# CompensationRegression.net
KiCad netlist of a schematic drawn in Altium Designer
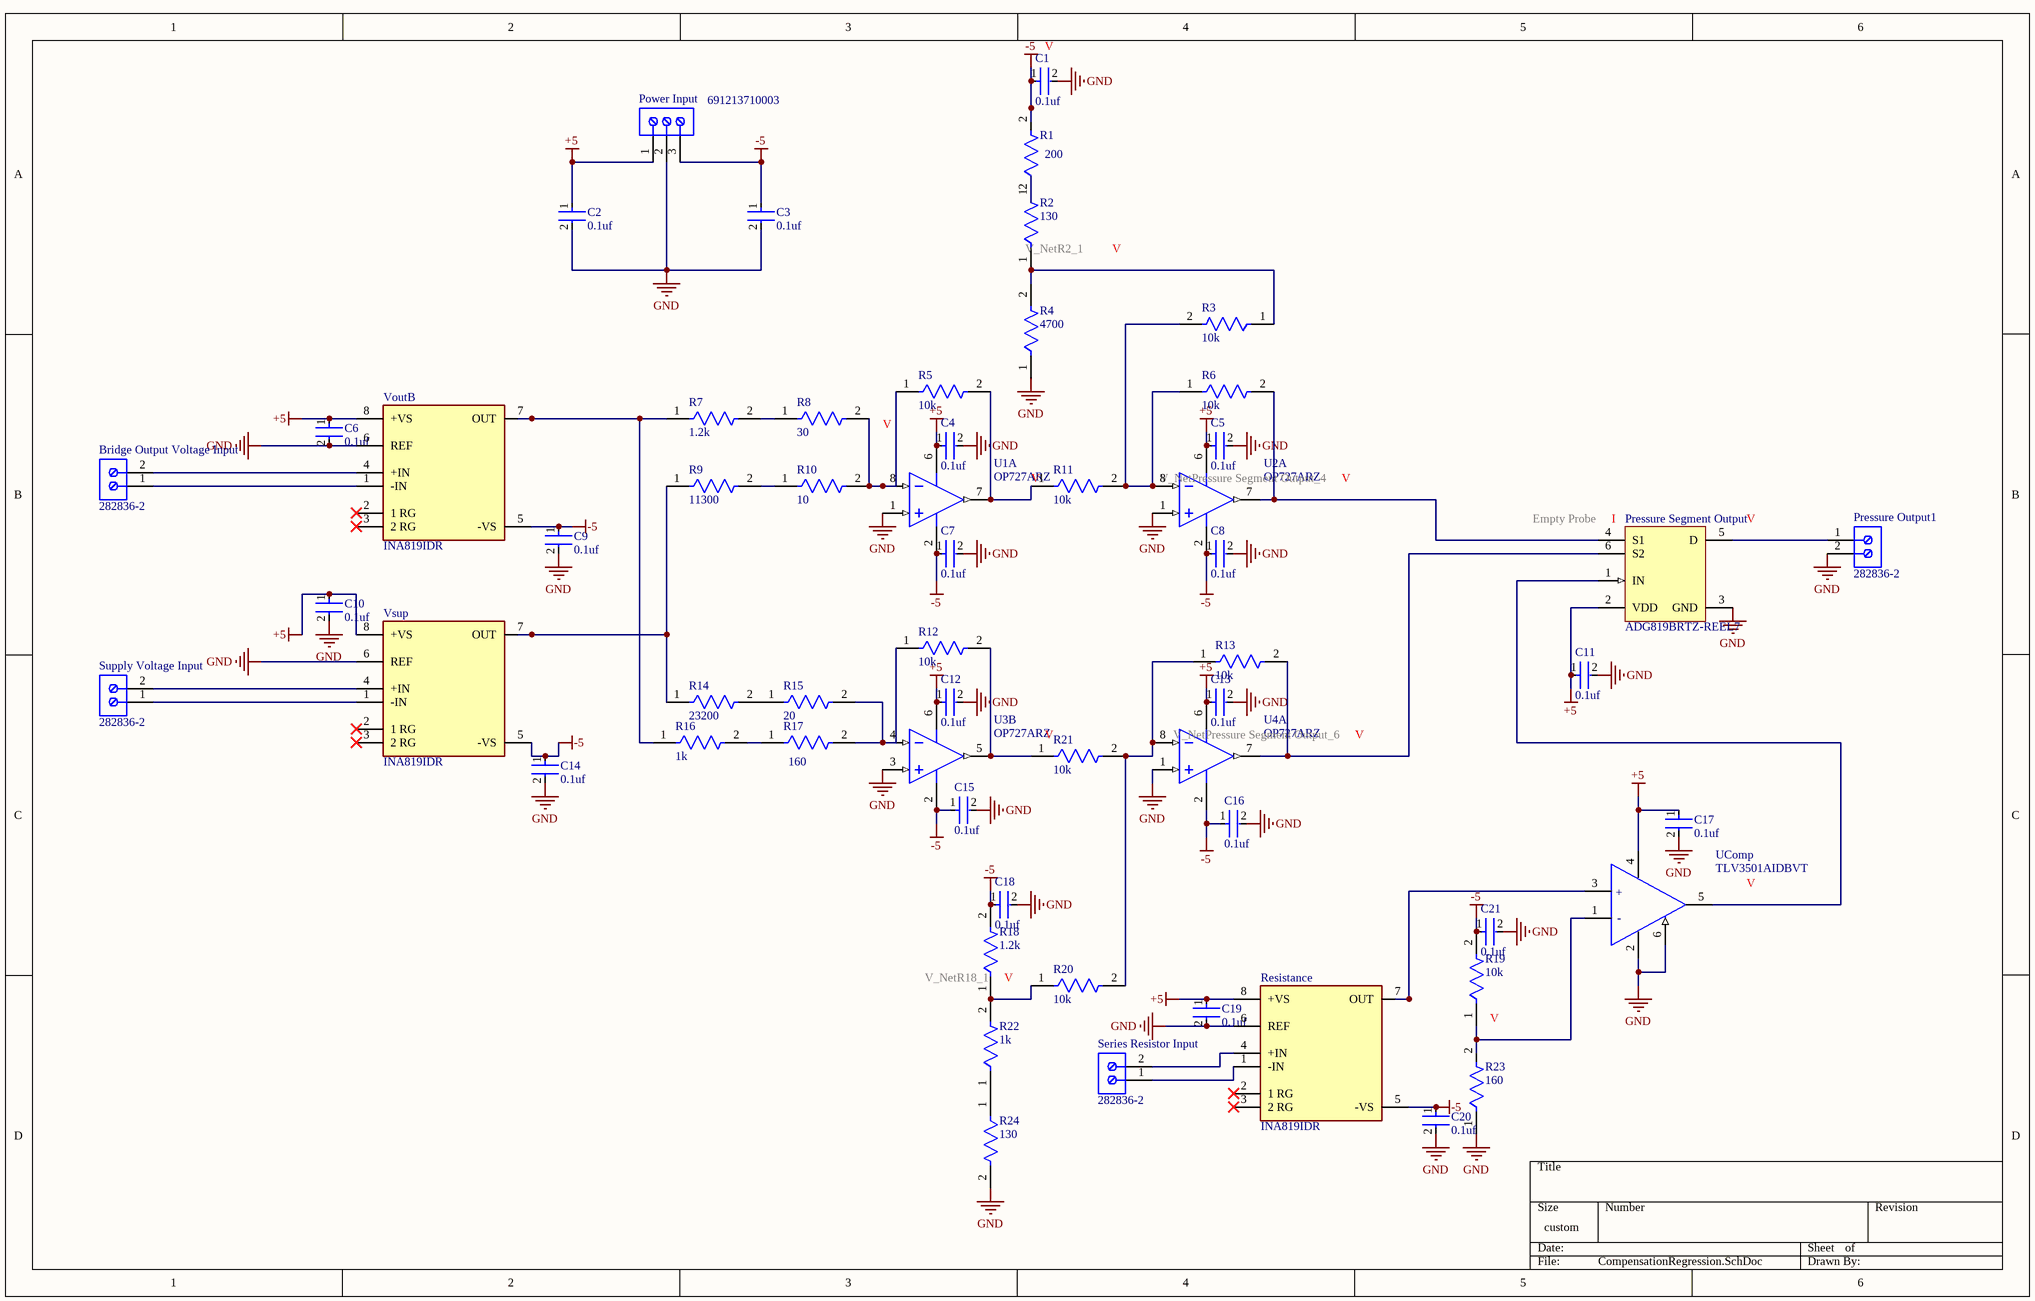
[diagram p0: CompensationRegression.SchDoc]

(export (version "E")
  (design (tool "Eeschema 10.0.6"))
  (components
    (comp (ref "Bridge Output Voltage Input")
      (value "282836-2")
      (footprint "TECO-282836-2_V")
      (description "Female Header, Pitch 5 mm, 1 x 2 Position, Height 10 mm, Tail Length 3.5 mm, Rohs, Bulk")
      (fields (field (name "VOLTAGE") "300V") (field (name "MANUFACTURER") "TE Connectivity"))
      (libsource (lib "Altium Content Vault") (part "CN-1P-F-TB2"))
    )
    (comp (ref "C1")
      (value "0.1uf")
      (footprint "FP-C0603C-CF-MFG")
      (description "CAP CER 0.1UF 50V X7R 0603")
      (fields (field (name "TOLERANCE") "0.1") (field (name "MANUFACTURER") "KEMET"))
      (libsource (lib "Altium Content Vault") (part "b4654b650e69147ec39a6b967a45e02"))
    )
    (comp (ref "C2")
      (value "0.1uf")
      (footprint "FP-C0603C-CF-MFG")
      (description "CAP CER 0.1UF 50V X7R 0603")
      (fields (field (name "TOLERANCE") "0.1") (field (name "MANUFACTURER") "KEMET"))
      (libsource (lib "Altium Content Vault") (part "b4654b650e69147ec39a6b967a45e02"))
    )
    (comp (ref "C3")
      (value "0.1uf")
      (footprint "FP-C0603C-CF-MFG")
      (description "CAP CER 0.1UF 50V X7R 0603")
      (fields (field (name "TOLERANCE") "0.1") (field (name "MANUFACTURER") "KEMET"))
      (libsource (lib "Altium Content Vault") (part "b4654b650e69147ec39a6b967a45e02"))
    )
    (comp (ref "C4")
      (value "0.1uf")
      (footprint "FP-C0603C-CF-MFG")
      (description "CAP CER 0.1UF 50V X7R 0603")
      (fields (field (name "TOLERANCE") "0.1") (field (name "MANUFACTURER") "KEMET"))
      (libsource (lib "Altium Content Vault") (part "b4654b650e69147ec39a6b967a45e02"))
    )
    (comp (ref "C5")
      (value "0.1uf")
      (footprint "FP-C0603C-CF-MFG")
      (description "CAP CER 0.1UF 50V X7R 0603")
      (fields (field (name "TOLERANCE") "0.1") (field (name "MANUFACTURER") "KEMET"))
      (libsource (lib "Altium Content Vault") (part "b4654b650e69147ec39a6b967a45e02"))
    )
    (comp (ref "C6")
      (value "0.1uf")
      (footprint "FP-C0603C-CF-MFG")
      (description "CAP CER 0.1UF 50V X7R 0603")
      (fields (field (name "TOLERANCE") "0.1") (field (name "MANUFACTURER") "KEMET"))
      (libsource (lib "Altium Content Vault") (part "b4654b650e69147ec39a6b967a45e02"))
    )
    (comp (ref "C7")
      (value "0.1uf")
      (footprint "FP-C0603C-CF-MFG")
      (description "CAP CER 0.1UF 50V X7R 0603")
      (fields (field (name "TOLERANCE") "0.1") (field (name "MANUFACTURER") "KEMET"))
      (libsource (lib "Altium Content Vault") (part "b4654b650e69147ec39a6b967a45e02"))
    )
    (comp (ref "C8")
      (value "0.1uf")
      (footprint "FP-C0603C-CF-MFG")
      (description "CAP CER 0.1UF 50V X7R 0603")
      (fields (field (name "TOLERANCE") "0.1") (field (name "MANUFACTURER") "KEMET"))
      (libsource (lib "Altium Content Vault") (part "b4654b650e69147ec39a6b967a45e02"))
    )
    (comp (ref "C9")
      (value "0.1uf")
      (footprint "FP-C0603C-CF-MFG")
      (description "CAP CER 0.1UF 50V X7R 0603")
      (fields (field (name "TOLERANCE") "0.1") (field (name "MANUFACTURER") "KEMET"))
      (libsource (lib "Altium Content Vault") (part "b4654b650e69147ec39a6b967a45e02"))
    )
    (comp (ref "C10")
      (value "0.1uf")
      (footprint "FP-C0603C-CF-MFG")
      (description "CAP CER 0.1UF 50V X7R 0603")
      (fields (field (name "TOLERANCE") "0.1") (field (name "MANUFACTURER") "KEMET"))
      (libsource (lib "Altium Content Vault") (part "b4654b650e69147ec39a6b967a45e02"))
    )
    (comp (ref "C11")
      (value "0.1uf")
      (footprint "FP-C0603C-CF-MFG")
      (description "CAP CER 0.1UF 50V X7R 0603")
      (fields (field (name "TOLERANCE") "0.1") (field (name "MANUFACTURER") "KEMET"))
      (libsource (lib "Altium Content Vault") (part "b4654b650e69147ec39a6b967a45e02"))
    )
    (comp (ref "C12")
      (value "0.1uf")
      (footprint "FP-C0603C-CF-MFG")
      (description "CAP CER 0.1UF 50V X7R 0603")
      (fields (field (name "TOLERANCE") "0.1") (field (name "MANUFACTURER") "KEMET"))
      (libsource (lib "Altium Content Vault") (part "b4654b650e69147ec39a6b967a45e02"))
    )
    (comp (ref "C13")
      (value "0.1uf")
      (footprint "FP-C0603C-CF-MFG")
      (description "CAP CER 0.1UF 50V X7R 0603")
      (fields (field (name "TOLERANCE") "0.1") (field (name "MANUFACTURER") "KEMET"))
      (libsource (lib "Altium Content Vault") (part "b4654b650e69147ec39a6b967a45e02"))
    )
    (comp (ref "C14")
      (value "0.1uf")
      (footprint "FP-C0603C-CF-MFG")
      (description "CAP CER 0.1UF 50V X7R 0603")
      (fields (field (name "TOLERANCE") "0.1") (field (name "MANUFACTURER") "KEMET"))
      (libsource (lib "Altium Content Vault") (part "b4654b650e69147ec39a6b967a45e02"))
    )
    (comp (ref "C15")
      (value "0.1uf")
      (footprint "FP-C0603C-CF-MFG")
      (description "CAP CER 0.1UF 50V X7R 0603")
      (fields (field (name "TOLERANCE") "0.1") (field (name "MANUFACTURER") "KEMET"))
      (libsource (lib "Altium Content Vault") (part "b4654b650e69147ec39a6b967a45e02"))
    )
    (comp (ref "C16")
      (value "0.1uf")
      (footprint "FP-C0603C-CF-MFG")
      (description "CAP CER 0.1UF 50V X7R 0603")
      (fields (field (name "TOLERANCE") "0.1") (field (name "MANUFACTURER") "KEMET"))
      (libsource (lib "Altium Content Vault") (part "b4654b650e69147ec39a6b967a45e02"))
    )
    (comp (ref "C17")
      (value "0.1uf")
      (footprint "FP-C0603C-CF-MFG")
      (description "CAP CER 0.1UF 50V X7R 0603")
      (fields (field (name "TOLERANCE") "0.1") (field (name "MANUFACTURER") "KEMET"))
      (libsource (lib "Altium Content Vault") (part "b4654b650e69147ec39a6b967a45e02"))
    )
    (comp (ref "C18")
      (value "0.1uf")
      (footprint "FP-C0603C-CF-MFG")
      (description "CAP CER 0.1UF 50V X7R 0603")
      (fields (field (name "TOLERANCE") "0.1") (field (name "MANUFACTURER") "KEMET"))
      (libsource (lib "Altium Content Vault") (part "b4654b650e69147ec39a6b967a45e02"))
    )
    (comp (ref "C19")
      (value "0.1uf")
      (footprint "FP-C0603C-CF-MFG")
      (description "CAP CER 0.1UF 50V X7R 0603")
      (fields (field (name "TOLERANCE") "0.1") (field (name "MANUFACTURER") "KEMET"))
      (libsource (lib "Altium Content Vault") (part "b4654b650e69147ec39a6b967a45e02"))
    )
    (comp (ref "C20")
      (value "0.1uf")
      (footprint "FP-C0603C-CF-MFG")
      (description "CAP CER 0.1UF 50V X7R 0603")
      (fields (field (name "TOLERANCE") "0.1") (field (name "MANUFACTURER") "KEMET"))
      (libsource (lib "Altium Content Vault") (part "b4654b650e69147ec39a6b967a45e02"))
    )
    (comp (ref "C21")
      (value "0.1uf")
      (footprint "FP-C0603C-CF-MFG")
      (description "CAP CER 0.1UF 50V X7R 0603")
      (fields (field (name "TOLERANCE") "0.1") (field (name "MANUFACTURER") "KEMET"))
      (libsource (lib "Altium Content Vault") (part "b4654b650e69147ec39a6b967a45e02"))
    )
    (comp (ref "Power Input")
      (value "691213710003")
      (footprint "691213710003")
      (fields (field (name "VOLTAGE") "300V"))
      (libsource (lib "Altium Content Vault") (part "TBL - 1R - 03P - Screw"))
    )
    (comp (ref "Pressure Output1")
      (value "282836-2")
      (footprint "TECO-282836-2_V")
      (description "Female Header, Pitch 5 mm, 1 x 2 Position, Height 10 mm, Tail Length 3.5 mm, Rohs, Bulk")
      (fields (field (name "VOLTAGE") "300V") (field (name "MANUFACTURER") "TE Connectivity"))
      (libsource (lib "Altium Content Vault") (part "CN-1P-F-TB2"))
    )
    (comp (ref "Pressure Segment Output")
      (value "ADG819BRTZ-REEL7")
      (footprint "ADI-RJ-6_N")
      (description "0.5 Ohm, CMOS, 1.8 to 5.5 V, 2:1 Mux / SPDT Switch, -40 to 125 degC, 6-pin SOT23 (RJ-6), Reel")
      (fields (field (name "MANUFACTURER") "Analog Devices"))
      (libsource (lib "Altium Content Vault") (part "ADI-ADG819-RJ-6"))
    )
    (comp (ref "R1")
      (value "200")
      (footprint "FP-CRCW0603-e3-MFG")
      (description "RES Thick Film, 200Ω, 1%, 0.1W, 100ppm/°C, 0603")
      (fields (field (name "TOLERANCE") "1%"))
      (libsource (lib "Altium Content Vault") (part "1029c3af85768c4190bb7ad29bc67b5"))
    )
    (comp (ref "R2")
      (value "130")
      (footprint "FP-CRCW0603-e3-MFG")
      (description "RES Thick Film, 130Ω, 1%, 0.1W, 100ppm/°C, 0603")
      (fields (field (name "TOLERANCE") "1%"))
      (libsource (lib "Altium Content Vault") (part "1029c3af85768c4190bb7ad29bc67b5"))
    )
    (comp (ref "R3")
      (value "10k")
      (footprint "FP-RT0603-MFG")
      (description "RES SMD 10K OHM 1% 1/10W 0603")
      (fields
        (field (name "MANUFACTURER") "Yageo")
        (field (name "OCTOPART") "https://octopart.com/rt0603fre0710kl-yageo-40009243")
      )
      (libsource (lib "Altium Content Vault") (part "1029c3af85768c4190bb7ad29bc67b5"))
    )
    (comp (ref "R4")
      (value "4700")
      (footprint "FP-MCT0603-MFG")
      (description "RES SMD 100 OHM 1% 1/8W 0603")
      (fields (field (name "TOLERANCE") "0.1%"))
      (libsource (lib "Altium Content Vault") (part "1029c3af85768c4190bb7ad29bc67b5"))
    )
    (comp (ref "R5")
      (value "10k")
      (footprint "FP-RT0603-MFG")
      (description "RES SMD 10K OHM 1% 1/10W 0603")
      (fields
        (field (name "MANUFACTURER") "Yageo")
        (field (name "OCTOPART") "https://octopart.com/rt0603fre0710kl-yageo-40009243")
      )
      (libsource (lib "Altium Content Vault") (part "1029c3af85768c4190bb7ad29bc67b5"))
    )
    (comp (ref "R6")
      (value "10k")
      (footprint "FP-RT0603-MFG")
      (description "RES SMD 10K OHM 1% 1/10W 0603")
      (fields
        (field (name "MANUFACTURER") "Yageo")
        (field (name "OCTOPART") "https://octopart.com/rt0603fre0710kl-yageo-40009243")
      )
      (libsource (lib "Altium Content Vault") (part "1029c3af85768c4190bb7ad29bc67b5"))
    )
    (comp (ref "R7")
      (value "1.2k")
      (footprint "FP-RG1005-IPC_A")
      (fields (field (name "TOLERANCE") "0.05%"))
      (libsource (lib "Altium Content Vault") (part "1029c3af85768c4190bb7ad29bc67b5"))
    )
    (comp (ref "R8")
      (value "30")
      (footprint "FP-CRCW0805-e3-MFG")
      (description "RES SMD 30 OHM 1% 1/8W 0805")
      (fields
        (field (name "OCTOPART") "https://octopart.com/crcw080530r0fkea-vishay-39861726")
        (field (name "TOLERANCE") "1%")
      )
      (libsource (lib "Altium Content Vault") (part "1029c3af85768c4190bb7ad29bc67b5"))
    )
    (comp (ref "R9")
      (value "11300")
      (footprint "FP-RP73P-1E-MFG")
      (description "RP73P 0402 11.3Ω 0.1W 25ppm/°C 0.10% 50V")
      (fields
        (field (name "MANUFACTURER") "TE Connectivity")
        (field (name "MANUFACTURER PART NUMBER") "RP73PF1E11R3BTDF")
      )
      (libsource (lib "Altium Content Vault") (part "1029c3af85768c4190bb7ad29bc67b5"))
    )
    (comp (ref "R10")
      (value "10")
      (footprint "FP-CRCW0603-e3-IPC_A")
      (description "RES Thick Film, 10Ω, 1%, 0.1W, 100ppm/°C, 0603")
      (fields (field (name "TOLERANCE") "1%"))
      (libsource (lib "Altium Content Vault") (part "1029c3af85768c4190bb7ad29bc67b5"))
    )
    (comp (ref "R11")
      (value "10k")
      (footprint "FP-RT0603-MFG")
      (description "RES SMD 10K OHM 1% 1/10W 0603")
      (fields
        (field (name "MANUFACTURER") "Yageo")
        (field (name "OCTOPART") "https://octopart.com/rt0603fre0710kl-yageo-40009243")
      )
      (libsource (lib "Altium Content Vault") (part "1029c3af85768c4190bb7ad29bc67b5"))
    )
    (comp (ref "R12")
      (value "10k")
      (footprint "FP-RT0603-MFG")
      (description "RES SMD 10K OHM 1% 1/10W 0603")
      (fields
        (field (name "MANUFACTURER") "Yageo")
        (field (name "OCTOPART") "https://octopart.com/rt0603fre0710kl-yageo-40009243")
      )
      (libsource (lib "Altium Content Vault") (part "1029c3af85768c4190bb7ad29bc67b5"))
    )
    (comp (ref "R13")
      (value "10k")
      (footprint "FP-RT0603-MFG")
      (description "RES SMD 10K OHM 1% 1/10W 0603")
      (fields
        (field (name "MANUFACTURER") "Yageo")
        (field (name "OCTOPART") "https://octopart.com/rt0603fre0710kl-yageo-40009243")
      )
      (libsource (lib "Altium Content Vault") (part "1029c3af85768c4190bb7ad29bc67b5"))
    )
    (comp (ref "R14")
      (value "23200")
      (footprint "FP-CRCW0603-e3-IPC_A")
      (description "RES Thick Film, 10Ω, 1%, 0.1W, 100ppm/°C, 0603\r\n\r\nShould be RMCF0603FT23K2")
      (fields (field (name "TOLERANCE") "1%"))
      (libsource (lib "Altium Content Vault") (part "1029c3af85768c4190bb7ad29bc67b5"))
    )
    (comp (ref "R15")
      (value "20")
      (footprint "FP-CRCW0402-e3-IPC_C")
      (description "RES Thick Film, 20Ω, 1%, 0.063W, 100ppm/°C, 0402")
      (fields (field (name "TOLERANCE") "1%"))
      (libsource (lib "Altium Content Vault") (part "1029c3af85768c4190bb7ad29bc67b5"))
    )
    (comp (ref "R16")
      (value "1k")
      (footprint "FP-CRCW0402-e3-MFG")
      (description "RES Thick Film, 1kΩ, 1%, 0.063W, 100ppm/°C, 0402")
      (fields (field (name "TOLERANCE") "1%"))
      (libsource (lib "Altium Content Vault") (part "1029c3af85768c4190bb7ad29bc67b5"))
    )
    (comp (ref "R17")
      (value "160")
      (footprint "FP-CRCW0402-e3-IPC_B")
      (description "RES Thick Film, 160Ω, 1%, 0.063W, 100ppm/°C, 0402")
      (fields (field (name "TOLERANCE") "1%"))
      (libsource (lib "Altium Content Vault") (part "1029c3af85768c4190bb7ad29bc67b5"))
    )
    (comp (ref "R18")
      (value "1.2k")
      (footprint "FP-RG1005-IPC_A")
      (description "Automotive Metal Thin Film Chip Resistor, 0402, 1.2kΩ, 0.05%, 25ppm/°C, 0.0625W, 75V")
      (fields (field (name "TOLERANCE") "0.05%"))
      (libsource (lib "Altium Content Vault") (part "1029c3af85768c4190bb7ad29bc67b5"))
    )
    (comp (ref "R19")
      (value "10k")
      (footprint "FP-RT0603-MFG")
      (description "RES SMD 10K OHM 1% 1/10W 0603")
      (fields
        (field (name "MANUFACTURER") "Yageo")
        (field (name "OCTOPART") "https://octopart.com/rt0603fre0710kl-yageo-40009243")
      )
      (libsource (lib "Altium Content Vault") (part "1029c3af85768c4190bb7ad29bc67b5"))
    )
    (comp (ref "R20")
      (value "10k")
      (footprint "FP-RT0603-MFG")
      (description "RES SMD 10K OHM 1% 1/10W 0603")
      (fields
        (field (name "MANUFACTURER") "Yageo")
        (field (name "OCTOPART") "https://octopart.com/rt0603fre0710kl-yageo-40009243")
      )
      (libsource (lib "Altium Content Vault") (part "1029c3af85768c4190bb7ad29bc67b5"))
    )
    (comp (ref "R21")
      (value "10k")
      (footprint "FP-RT0603-MFG")
      (description "RES SMD 10K OHM 1% 1/10W 0603")
      (fields
        (field (name "MANUFACTURER") "Yageo")
        (field (name "OCTOPART") "https://octopart.com/rt0603fre0710kl-yageo-40009243")
      )
      (libsource (lib "Altium Content Vault") (part "1029c3af85768c4190bb7ad29bc67b5"))
    )
    (comp (ref "R22")
      (value "1k")
      (footprint "FP-CRCW0402-e3-MFG")
      (description "RES Thick Film, 1kΩ, 1%, 0.063W, 100ppm/°C, 0402")
      (fields (field (name "TOLERANCE") "1%"))
      (libsource (lib "Altium Content Vault") (part "1029c3af85768c4190bb7ad29bc67b5"))
    )
    (comp (ref "R23")
      (value "160")
      (footprint "FP-CRCW0402-e3-IPC_B")
      (description "RES Thick Film, 160Ω, 1%, 0.063W, 100ppm/°C, 0402")
      (fields (field (name "TOLERANCE") "1%"))
      (libsource (lib "Altium Content Vault") (part "1029c3af85768c4190bb7ad29bc67b5"))
    )
    (comp (ref "R24")
      (value "130")
      (footprint "FP-CRCW0603-e3-MFG")
      (description "RES Thick Film, 130Ω, 1%, 0.1W, 100ppm/°C, 0603")
      (fields (field (name "TOLERANCE") "1%"))
      (libsource (lib "Altium Content Vault") (part "1029c3af85768c4190bb7ad29bc67b5"))
    )
    (comp (ref "Resistance")
      (value "INA819IDR")
      (footprint "FP-D0008A-MFG")
      (description "IC INST AMP 1 CIRCUIT 8SOIC")
      (libsource (lib "Altium Content Vault") (part "8571ca1dc6e78685731e0a9738c9e90"))
    )
    (comp (ref "Series Resistor Input")
      (value "282836-2")
      (footprint "TECO-282836-2_V")
      (description "Female Header, Pitch 5 mm, 1 x 2 Position, Height 10 mm, Tail Length 3.5 mm, Rohs, Bulk")
      (fields (field (name "VOLTAGE") "300V") (field (name "MANUFACTURER") "TE Connectivity"))
      (libsource (lib "Altium Content Vault") (part "CN-1P-F-TB2"))
    )
    (comp (ref "Supply Voltage Input")
      (value "282836-2")
      (footprint "TECO-282836-2_V")
      (description "Female Header, Pitch 5 mm, 1 x 2 Position, Height 10 mm, Tail Length 3.5 mm, Rohs, Bulk")
      (fields (field (name "VOLTAGE") "300V") (field (name "MANUFACTURER") "TE Connectivity"))
      (libsource (lib "Altium Content Vault") (part "CN-1P-F-TB2"))
    )
    (comp (ref "U1")
      (value "OP727ARZ")
      (footprint "ADI-R-8_L")
      (fields (field (name "GENERIC PART NUMBER") "OP727") (field (name "MANUFACTURER") "Analog Devices"))
      (libsource (lib "Altium Content Vault") (part "ADI-OP249_727-R-8"))
    )
    (comp (ref "U2")
      (value "OP727ARZ")
      (footprint "ADI-R-8_L")
      (fields (field (name "GENERIC PART NUMBER") "OP727") (field (name "MANUFACTURER") "Analog Devices"))
      (libsource (lib "Altium Content Vault") (part "ADI-OP249_727-R-8"))
    )
    (comp (ref "U3")
      (value "OP727ARZ")
      (footprint "ADI-R-8_L")
      (fields (field (name "GENERIC PART NUMBER") "OP727") (field (name "MANUFACTURER") "Analog Devices"))
      (libsource (lib "Altium Content Vault") (part "ADI-OP249_727-R-8"))
    )
    (comp (ref "U4")
      (value "OP727ARZ")
      (footprint "ADI-R-8_L")
      (fields (field (name "GENERIC PART NUMBER") "OP727") (field (name "MANUFACTURER") "Analog Devices"))
      (libsource (lib "Altium Content Vault") (part "ADI-OP249_727-R-8"))
    )
    (comp (ref "UComp")
      (value "TLV3501AIDBVT")
      (footprint "FP-DBV0006A-MFG")
      (description "IC COMP 4.5NS R-R HS SOT23-6")
      (fields
        (field (name "MANUFACTURER") "Texas Instruments")
        (field (name "OCTOPART") "https://octopart.com/tlv3501aidbvt-texas+instruments-428399")
      )
      (libsource (lib "Altium Content Vault") (part "0ecce7053b56ec2eec74f62614cfafa"))
    )
    (comp (ref "VoutB")
      (value "INA819IDR")
      (footprint "FP-D0008A-MFG")
      (description "IC INST AMP 1 CIRCUIT 8SOIC")
      (libsource (lib "Altium Content Vault") (part "8571ca1dc6e78685731e0a9738c9e90"))
    )
    (comp (ref "Vsup")
      (value "INA819IDR")
      (footprint "FP-D0008A-MFG")
      (description "IC INST AMP 1 CIRCUIT 8SOIC")
      (libsource (lib "Altium Content Vault") (part "8571ca1dc6e78685731e0a9738c9e90"))
    )
  )
  (nets
    (net (code "1") (name "+5") (class "Default")
      (node (ref "C10") (pin "1") (pinfunction "1_1") (pintype "passive"))
      (node (ref "C11") (pin "1") (pinfunction "1_1") (pintype "passive"))
      (node (ref "C12") (pin "1") (pinfunction "1_1") (pintype "passive"))
      (node (ref "C13") (pin "1") (pinfunction "1_1") (pintype "passive"))
      (node (ref "C17") (pin "1") (pinfunction "1_1") (pintype "passive"))
      (node (ref "C19") (pin "1") (pinfunction "1_1") (pintype "passive"))
      (node (ref "C2") (pin "1") (pinfunction "1_1") (pintype "passive"))
      (node (ref "C4") (pin "1") (pinfunction "1_1") (pintype "passive"))
      (node (ref "C5") (pin "1") (pinfunction "1_1") (pintype "passive"))
      (node (ref "C6") (pin "1") (pinfunction "1_1") (pintype "passive"))
      (node (ref "Power Input") (pin "1") (pinfunction "1_1") (pintype "passive"))
      (node (ref "Pressure Segment Output") (pin "2") (pinfunction "VDD_2") (pintype "power_in"))
      (node (ref "Resistance") (pin "8") (pinfunction "+VS_8") (pintype "power_in"))
      (node (ref "U1") (pin "6") (pinfunction "+V_6") (pintype "power_in"))
      (node (ref "U2") (pin "6") (pinfunction "+V_6") (pintype "power_in"))
      (node (ref "U3") (pin "6") (pinfunction "+V_6") (pintype "power_in"))
      (node (ref "U4") (pin "6") (pinfunction "+V_6") (pintype "power_in"))
      (node (ref "UComp") (pin "4") (pinfunction "V+_4") (pintype "power_in"))
      (node (ref "VoutB") (pin "8") (pinfunction "+VS_8") (pintype "power_in"))
      (node (ref "Vsup") (pin "8") (pinfunction "+VS_8") (pintype "power_in"))
    )
    (net (code "2") (name "-5") (class "Default")
      (node (ref "C1") (pin "1") (pinfunction "1_1") (pintype "passive"))
      (node (ref "C14") (pin "1") (pinfunction "1_1") (pintype "passive"))
      (node (ref "C15") (pin "1") (pinfunction "1_1") (pintype "passive"))
      (node (ref "C16") (pin "1") (pinfunction "1_1") (pintype "passive"))
      (node (ref "C18") (pin "1") (pinfunction "1_1") (pintype "passive"))
      (node (ref "C20") (pin "1") (pinfunction "1_1") (pintype "passive"))
      (node (ref "C21") (pin "1") (pinfunction "1_1") (pintype "passive"))
      (node (ref "C3") (pin "1") (pinfunction "1_1") (pintype "passive"))
      (node (ref "C7") (pin "1") (pinfunction "1_1") (pintype "passive"))
      (node (ref "C8") (pin "1") (pinfunction "1_1") (pintype "passive"))
      (node (ref "C9") (pin "1") (pinfunction "1_1") (pintype "passive"))
      (node (ref "Power Input") (pin "3") (pinfunction "3_3") (pintype "passive"))
      (node (ref "R1") (pin "2") (pinfunction "2_2") (pintype "passive"))
      (node (ref "R18") (pin "2") (pinfunction "2_2") (pintype "passive"))
      (node (ref "R19") (pin "2") (pinfunction "2_2") (pintype "passive"))
      (node (ref "Resistance") (pin "5") (pinfunction "-VS_5") (pintype "power_in"))
      (node (ref "U1") (pin "2") (pinfunction "-V_2") (pintype "power_in"))
      (node (ref "U2") (pin "2") (pinfunction "-V_2") (pintype "power_in"))
      (node (ref "U3") (pin "2") (pinfunction "-V_2") (pintype "power_in"))
      (node (ref "U4") (pin "2") (pinfunction "-V_2") (pintype "power_in"))
      (node (ref "VoutB") (pin "5") (pinfunction "-VS_5") (pintype "power_in"))
      (node (ref "Vsup") (pin "5") (pinfunction "-VS_5") (pintype "power_in"))
    )
    (net (code "3") (name "GND") (class "Default")
      (node (ref "C1") (pin "2") (pinfunction "2_2") (pintype "passive"))
      (node (ref "C10") (pin "2") (pinfunction "2_2") (pintype "passive"))
      (node (ref "C11") (pin "2") (pinfunction "2_2") (pintype "passive"))
      (node (ref "C12") (pin "2") (pinfunction "2_2") (pintype "passive"))
      (node (ref "C13") (pin "2") (pinfunction "2_2") (pintype "passive"))
      (node (ref "C14") (pin "2") (pinfunction "2_2") (pintype "passive"))
      (node (ref "C15") (pin "2") (pinfunction "2_2") (pintype "passive"))
      (node (ref "C16") (pin "2") (pinfunction "2_2") (pintype "passive"))
      (node (ref "C17") (pin "2") (pinfunction "2_2") (pintype "passive"))
      (node (ref "C18") (pin "2") (pinfunction "2_2") (pintype "passive"))
      (node (ref "C19") (pin "2") (pinfunction "2_2") (pintype "passive"))
      (node (ref "C2") (pin "2") (pinfunction "2_2") (pintype "passive"))
      (node (ref "C20") (pin "2") (pinfunction "2_2") (pintype "passive"))
      (node (ref "C21") (pin "2") (pinfunction "2_2") (pintype "passive"))
      (node (ref "C3") (pin "2") (pinfunction "2_2") (pintype "passive"))
      (node (ref "C4") (pin "2") (pinfunction "2_2") (pintype "passive"))
      (node (ref "C5") (pin "2") (pinfunction "2_2") (pintype "passive"))
      (node (ref "C6") (pin "2") (pinfunction "2_2") (pintype "passive"))
      (node (ref "C7") (pin "2") (pinfunction "2_2") (pintype "passive"))
      (node (ref "C8") (pin "2") (pinfunction "2_2") (pintype "passive"))
      (node (ref "C9") (pin "2") (pinfunction "2_2") (pintype "passive"))
      (node (ref "Power Input") (pin "2") (pinfunction "2_2") (pintype "passive"))
      (node (ref "Pressure Output1") (pin "2") (pinfunction "2_2") (pintype "passive"))
      (node (ref "Pressure Segment Output") (pin "3") (pinfunction "GND_3") (pintype "power_in"))
      (node (ref "R23") (pin "1") (pinfunction "1_1") (pintype "passive"))
      (node (ref "R24") (pin "2") (pinfunction "2_2") (pintype "passive"))
      (node (ref "R4") (pin "1") (pinfunction "1_1") (pintype "passive"))
      (node (ref "Resistance") (pin "6") (pinfunction "REF_6") (pintype "passive"))
      (node (ref "U1") (pin "1") (pinfunction "+IN_A_1") (pintype "input"))
      (node (ref "U2") (pin "1") (pinfunction "+IN_A_1") (pintype "input"))
      (node (ref "U3") (pin "3") (pinfunction "+IN_B_3") (pintype "input"))
      (node (ref "U4") (pin "1") (pinfunction "+IN_A_1") (pintype "input"))
      (node (ref "UComp") (pin "2") (pinfunction "V-_2") (pintype "power_in"))
      (node (ref "UComp") (pin "6") (pinfunction "SHDN_6") (pintype "input"))
      (node (ref "VoutB") (pin "6") (pinfunction "REF_6") (pintype "passive"))
      (node (ref "Vsup") (pin "6") (pinfunction "REF_6") (pintype "passive"))
    )
    (net (code "4") (name "Net-(Pressure Segment Output-D)") (class "Default")
      (node (ref "Pressure Output1") (pin "1") (pinfunction "1_1") (pintype "passive"))
      (node (ref "Pressure Segment Output") (pin "5") (pinfunction "D_5") (pintype "passive"))
    )
    (net (code "5") (name "Net-(Pressure Segment Output-IN)") (class "Default")
      (node (ref "Pressure Segment Output") (pin "1") (pinfunction "IN_1") (pintype "input"))
      (node (ref "UComp") (pin "5") (pinfunction "OUT_5") (pintype "passive"))
    )
    (net (code "6") (name "Net-(Pressure Segment Output-S1)") (class "Default")
      (node (ref "Pressure Segment Output") (pin "4") (pinfunction "S1_4") (pintype "passive"))
      (node (ref "R6") (pin "2") (pinfunction "2_2") (pintype "passive"))
      (node (ref "U2") (pin "7") (pinfunction "OUT_A_7") (pintype "output"))
    )
    (net (code "7") (name "Net-(Pressure Segment Output-S2)") (class "Default")
      (node (ref "Pressure Segment Output") (pin "6") (pinfunction "S2_6") (pintype "passive"))
      (node (ref "R13") (pin "2") (pinfunction "2_2") (pintype "passive"))
      (node (ref "U4") (pin "7") (pinfunction "OUT_A_7") (pintype "output"))
    )
    (net (code "8") (name "Net-(R1-Pad1)") (class "Default")
      (node (ref "R1") (pin "1") (pinfunction "1_1") (pintype "passive"))
      (node (ref "R2") (pin "2") (pinfunction "2_2") (pintype "passive"))
    )
    (net (code "9") (name "Net-(R2-Pad1)") (class "Default")
      (node (ref "R2") (pin "1") (pinfunction "1_1") (pintype "passive"))
      (node (ref "R3") (pin "1") (pinfunction "1_1") (pintype "passive"))
      (node (ref "R4") (pin "2") (pinfunction "2_2") (pintype "passive"))
    )
    (net (code "10") (name "Net-(R7-Pad2)") (class "Default")
      (node (ref "R7") (pin "2") (pinfunction "2_2") (pintype "passive"))
      (node (ref "R8") (pin "1") (pinfunction "1_1") (pintype "passive"))
    )
    (net (code "11") (name "Net-(R10-Pad1)") (class "Default")
      (node (ref "R10") (pin "1") (pinfunction "1_1") (pintype "passive"))
      (node (ref "R9") (pin "2") (pinfunction "2_2") (pintype "passive"))
    )
    (net (code "12") (name "Net-(R14-Pad2)") (class "Default")
      (node (ref "R14") (pin "2") (pinfunction "2_2") (pintype "passive"))
      (node (ref "R15") (pin "1") (pinfunction "1_1") (pintype "passive"))
    )
    (net (code "13") (name "Net-(R16-Pad2)") (class "Default")
      (node (ref "R16") (pin "2") (pinfunction "2_2") (pintype "passive"))
      (node (ref "R17") (pin "1") (pinfunction "1_1") (pintype "passive"))
    )
    (net (code "14") (name "Net-(R18-Pad1)") (class "Default")
      (node (ref "R18") (pin "1") (pinfunction "1_1") (pintype "passive"))
      (node (ref "R20") (pin "1") (pinfunction "1_1") (pintype "passive"))
      (node (ref "R22") (pin "2") (pinfunction "2_2") (pintype "passive"))
    )
    (net (code "15") (name "Net-(R22-Pad1)") (class "Default")
      (node (ref "R22") (pin "1") (pinfunction "1_1") (pintype "passive"))
      (node (ref "R24") (pin "1") (pinfunction "1_1") (pintype "passive"))
    )
    (net (code "16") (name "Net-(Resistance-+IN)") (class "Default")
      (node (ref "Resistance") (pin "4") (pinfunction "+IN_4") (pintype "tri_state"))
      (node (ref "Series Resistor Input") (pin "2") (pinfunction "2_2") (pintype "passive"))
    )
    (net (code "17") (name "Net-(Resistance--IN)") (class "Default")
      (node (ref "Resistance") (pin "1") (pinfunction "-IN_1") (pintype "tri_state"))
      (node (ref "Series Resistor Input") (pin "1") (pinfunction "1_1") (pintype "passive"))
    )
    (net (code "18") (name "Net-(Resistance-OUT)") (class "Default")
      (node (ref "Resistance") (pin "7") (pinfunction "OUT_7") (pintype "passive"))
      (node (ref "UComp") (pin "3") (pinfunction "+IN_3") (pintype "tri_state"))
    )
    (net (code "19") (name "Net-(U1A--IN_A)") (class "Default")
      (node (ref "R10") (pin "2") (pinfunction "2_2") (pintype "passive"))
      (node (ref "R5") (pin "1") (pinfunction "1_1") (pintype "passive"))
      (node (ref "R8") (pin "2") (pinfunction "2_2") (pintype "passive"))
      (node (ref "U1") (pin "8") (pinfunction "-IN_A_8") (pintype "input"))
    )
    (net (code "20") (name "Net-(U1A-OUT_A)") (class "Default")
      (node (ref "R11") (pin "1") (pinfunction "1_1") (pintype "passive"))
      (node (ref "R5") (pin "2") (pinfunction "2_2") (pintype "passive"))
      (node (ref "U1") (pin "7") (pinfunction "OUT_A_7") (pintype "output"))
    )
    (net (code "21") (name "Net-(U2A--IN_A)") (class "Default")
      (node (ref "R11") (pin "2") (pinfunction "2_2") (pintype "passive"))
      (node (ref "R3") (pin "2") (pinfunction "2_2") (pintype "passive"))
      (node (ref "R6") (pin "1") (pinfunction "1_1") (pintype "passive"))
      (node (ref "U2") (pin "8") (pinfunction "-IN_A_8") (pintype "input"))
    )
    (net (code "22") (name "Net-(U3B--IN_B)") (class "Default")
      (node (ref "R12") (pin "1") (pinfunction "1_1") (pintype "passive"))
      (node (ref "R15") (pin "2") (pinfunction "2_2") (pintype "passive"))
      (node (ref "R17") (pin "2") (pinfunction "2_2") (pintype "passive"))
      (node (ref "U3") (pin "4") (pinfunction "-IN_B_4") (pintype "input"))
    )
    (net (code "23") (name "Net-(U3B-OUT_B)") (class "Default")
      (node (ref "R12") (pin "2") (pinfunction "2_2") (pintype "passive"))
      (node (ref "R21") (pin "1") (pinfunction "1_1") (pintype "passive"))
      (node (ref "U3") (pin "5") (pinfunction "OUT_B_5") (pintype "output"))
    )
    (net (code "24") (name "Net-(U4A--IN_A)") (class "Default")
      (node (ref "R13") (pin "1") (pinfunction "1_1") (pintype "passive"))
      (node (ref "R20") (pin "2") (pinfunction "2_2") (pintype "passive"))
      (node (ref "R21") (pin "2") (pinfunction "2_2") (pintype "passive"))
      (node (ref "U4") (pin "8") (pinfunction "-IN_A_8") (pintype "input"))
    )
    (net (code "25") (name "Net-(UComp--IN)") (class "Default")
      (node (ref "R19") (pin "1") (pinfunction "1_1") (pintype "passive"))
      (node (ref "R23") (pin "2") (pinfunction "2_2") (pintype "passive"))
      (node (ref "UComp") (pin "1") (pinfunction "-IN_1") (pintype "tri_state"))
    )
    (net (code "26") (name "Net-(VoutB-+IN)") (class "Default")
      (node (ref "Bridge Output Voltage Input") (pin "2") (pinfunction "2_2") (pintype "passive"))
      (node (ref "VoutB") (pin "4") (pinfunction "+IN_4") (pintype "tri_state"))
    )
    (net (code "27") (name "Net-(VoutB--IN)") (class "Default")
      (node (ref "Bridge Output Voltage Input") (pin "1") (pinfunction "1_1") (pintype "passive"))
      (node (ref "VoutB") (pin "1") (pinfunction "-IN_1") (pintype "tri_state"))
    )
    (net (code "28") (name "Net-(VoutB-OUT)") (class "Default")
      (node (ref "R16") (pin "1") (pinfunction "1_1") (pintype "passive"))
      (node (ref "R7") (pin "1") (pinfunction "1_1") (pintype "passive"))
      (node (ref "VoutB") (pin "7") (pinfunction "OUT_7") (pintype "passive"))
    )
    (net (code "29") (name "Net-(Vsup-+IN)") (class "Default")
      (node (ref "Supply Voltage Input") (pin "2") (pinfunction "2_2") (pintype "passive"))
      (node (ref "Vsup") (pin "4") (pinfunction "+IN_4") (pintype "tri_state"))
    )
    (net (code "30") (name "Net-(Vsup--IN)") (class "Default")
      (node (ref "Supply Voltage Input") (pin "1") (pinfunction "1_1") (pintype "passive"))
      (node (ref "Vsup") (pin "1") (pinfunction "-IN_1") (pintype "tri_state"))
    )
    (net (code "31") (name "Net-(Vsup-OUT)") (class "Default")
      (node (ref "R14") (pin "1") (pinfunction "1_1") (pintype "passive"))
      (node (ref "R9") (pin "1") (pinfunction "1_1") (pintype "passive"))
      (node (ref "Vsup") (pin "7") (pinfunction "OUT_7") (pintype "passive"))
    )
    (net (code "32") (name "unconnected-(Resistance-1_RG-Pad2)") (class "Default")
      (node (ref "Resistance") (pin "2") (pinfunction "1_RG_2") (pintype "passive+no_connect"))
    )
    (net (code "33") (name "unconnected-(Resistance-2_RG-Pad3)") (class "Default")
      (node (ref "Resistance") (pin "3") (pinfunction "2_RG_3") (pintype "passive+no_connect"))
    )
    (net (code "34") (name "unconnected-(VoutB-1_RG-Pad2)") (class "Default")
      (node (ref "VoutB") (pin "2") (pinfunction "1_RG_2") (pintype "passive+no_connect"))
    )
    (net (code "35") (name "unconnected-(VoutB-2_RG-Pad3)") (class "Default")
      (node (ref "VoutB") (pin "3") (pinfunction "2_RG_3") (pintype "passive+no_connect"))
    )
    (net (code "36") (name "unconnected-(Vsup-1_RG-Pad2)") (class "Default")
      (node (ref "Vsup") (pin "2") (pinfunction "1_RG_2") (pintype "passive+no_connect"))
    )
    (net (code "37") (name "unconnected-(Vsup-2_RG-Pad3)") (class "Default")
      (node (ref "Vsup") (pin "3") (pinfunction "2_RG_3") (pintype "passive+no_connect"))
    )
  )
)
